# floppy_featherwing_rev_A.net
KiCad netlist of a schematic drawn in EAGLE
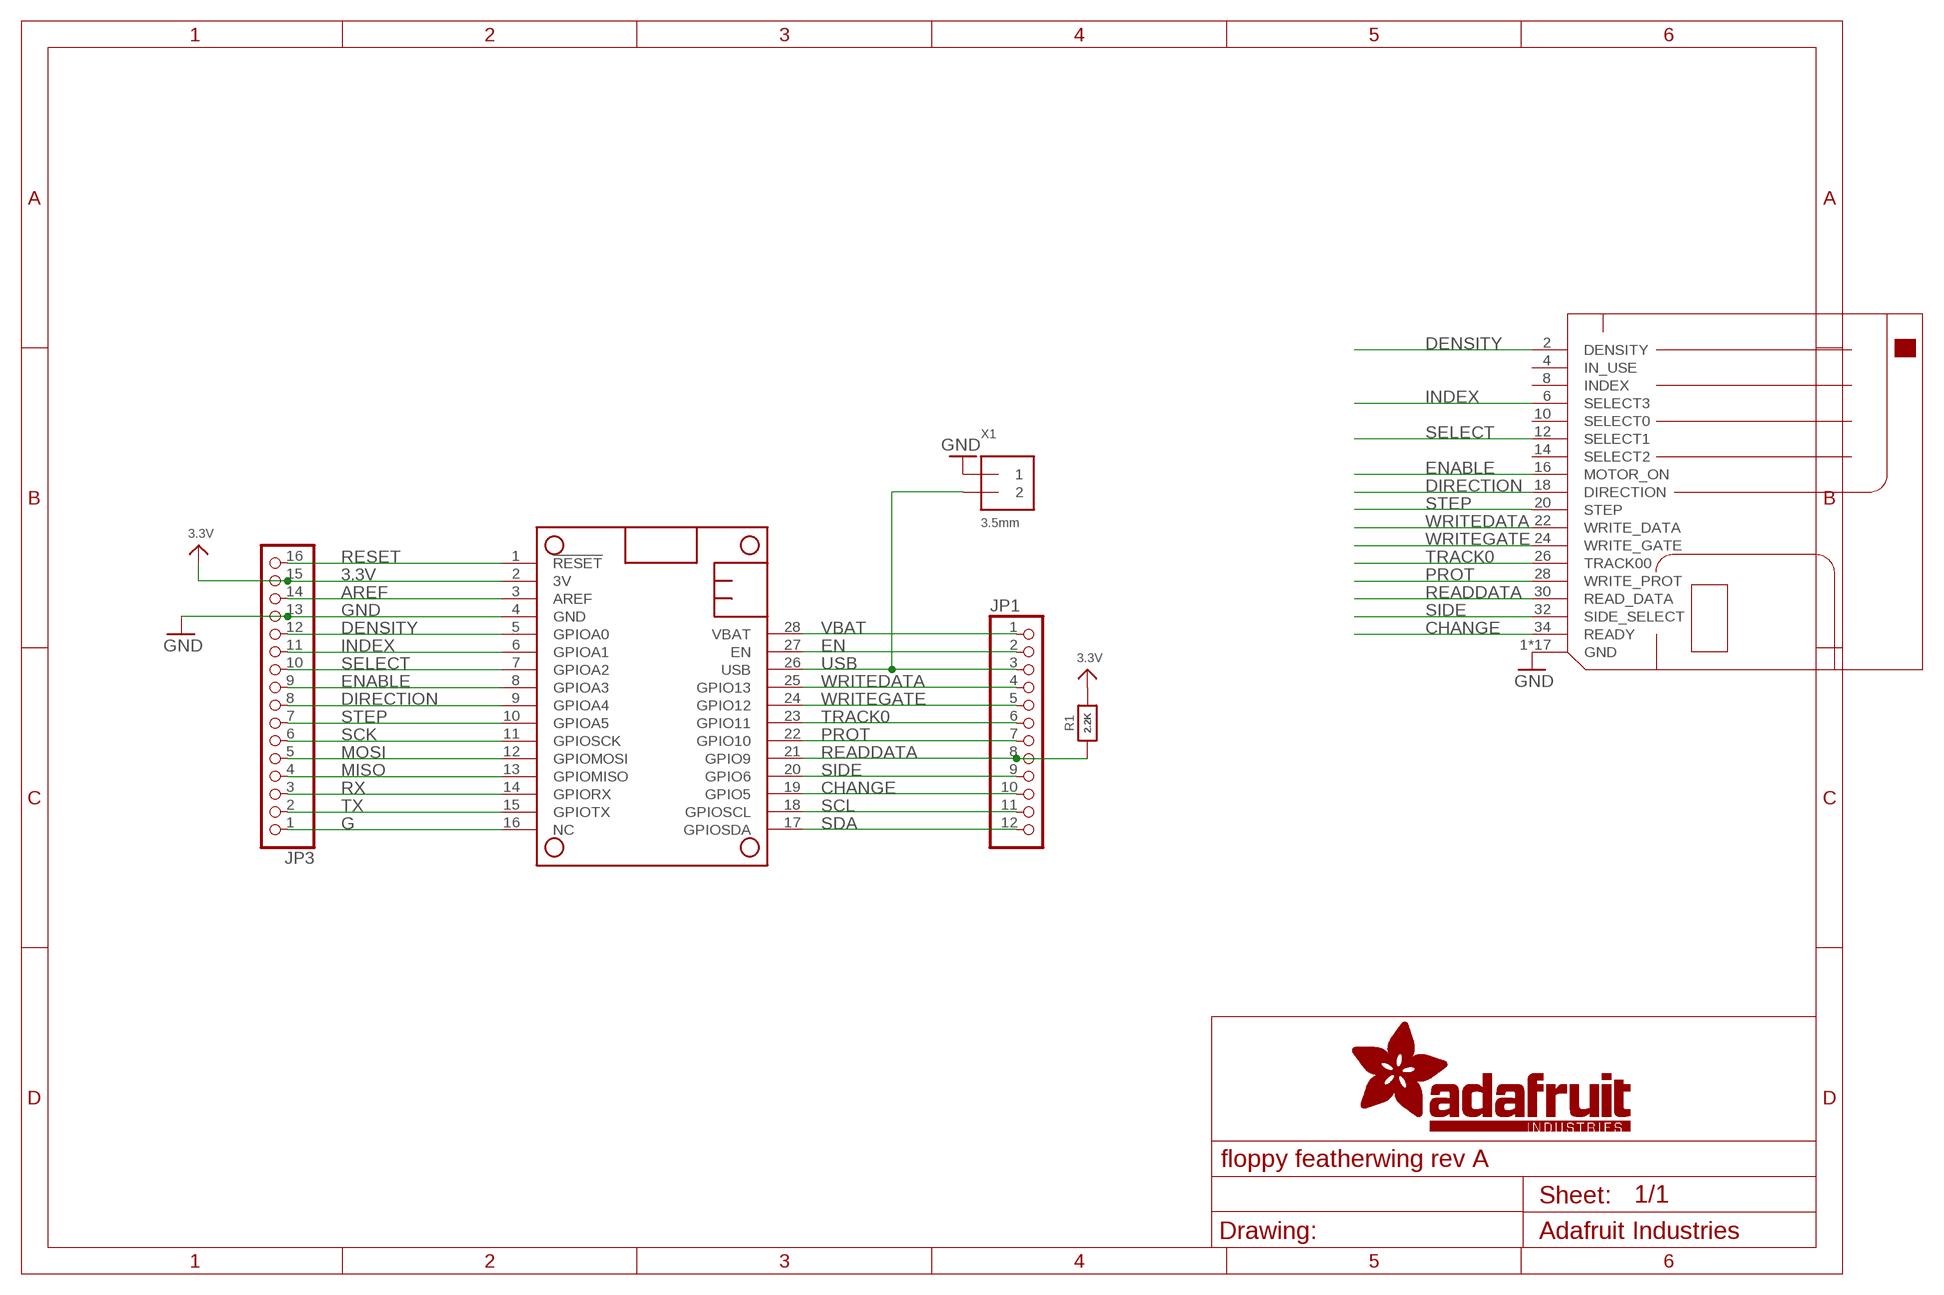
[diagram p0: schematic, sheet 1]

(export (version "E")
  (design (tool "Eeschema 10.0.6"))
  (components
    (comp (ref "FDD1")
      (value "FLOPPY_IDC_SHROUDED")
      (footprint "eagle-import:2X17_FLOPPY_IDC")
      (libsource (lib "eagle-import") (part "FLOPPY_IDC_SHROUDED"))
    )
    (comp (ref "JP1")
      (value "HEADER-1X12")
      (footprint "eagle-import:1X12_ROUND")
      (libsource (lib "eagle-import") (part "HEADER-1X12"))
    )
    (comp (ref "JP3")
      (value "HEADER-1X16ROUND")
      (footprint "eagle-import:1X16_ROUND")
      (libsource (lib "eagle-import") (part "HEADER-1X16ROUND"))
    )
    (comp (ref "MS1")
      (value "FEATHERWING")
      (footprint "eagle-import:FEATHERWING")
      (libsource (lib "eagle-import") (part "FEATHERWING"))
    )
    (comp (ref "R1")
      (value "2.2K")
      (footprint "eagle-import:0805-NO")
      (libsource (lib "eagle-import") (part "RESISTOR0805_NOOUTLINE"))
    )
    (comp (ref "X1")
      (value "3.5mm")
      (footprint "eagle-import:TERMBLOCK_1X2-3.5MM")
      (libsource (lib "eagle-import") (part "TERMBLOCK_1X2_3.5MM"))
    )
  )
  (nets
    (net (code "1") (name "/AREF") (class "Default")
      (node (ref "JP3") (pin "14") (pinfunction "14_14") (pintype "passive"))
      (node (ref "MS1") (pin "3") (pinfunction "AREF_3") (pintype "passive"))
    )
    (net (code "2") (name "/CHANGE") (class "Default")
      (node (ref "FDD1") (pin "34") (pinfunction "READY_34") (pintype "output"))
      (node (ref "JP1") (pin "10") (pinfunction "10_10") (pintype "passive"))
      (node (ref "MS1") (pin "19") (pinfunction "GPIO5_19") (pintype "bidirectional"))
    )
    (net (code "3") (name "/DENSITY") (class "Default")
      (node (ref "FDD1") (pin "2") (pinfunction "DENSITY_2") (pintype "input"))
      (node (ref "JP3") (pin "12") (pinfunction "12_12") (pintype "passive"))
      (node (ref "MS1") (pin "5") (pinfunction "GPIOA0_5") (pintype "bidirectional"))
    )
    (net (code "4") (name "/DIRECTION") (class "Default")
      (node (ref "FDD1") (pin "18") (pinfunction "DIRECTION_18") (pintype "input"))
      (node (ref "JP3") (pin "8") (pinfunction "8_8") (pintype "passive"))
      (node (ref "MS1") (pin "9") (pinfunction "GPIOA4_9") (pintype "bidirectional"))
    )
    (net (code "5") (name "/EN") (class "Default")
      (node (ref "JP1") (pin "2") (pinfunction "2_2") (pintype "passive"))
      (node (ref "MS1") (pin "27") (pinfunction "EN_27") (pintype "passive"))
    )
    (net (code "6") (name "/ENABLE") (class "Default")
      (node (ref "FDD1") (pin "16") (pinfunction "MOTOR_ON_16") (pintype "input"))
      (node (ref "JP3") (pin "9") (pinfunction "9_9") (pintype "passive"))
      (node (ref "MS1") (pin "8") (pinfunction "GPIOA3_8") (pintype "bidirectional"))
    )
    (net (code "7") (name "/G") (class "Default")
      (node (ref "JP3") (pin "1") (pinfunction "1_1") (pintype "passive"))
      (node (ref "MS1") (pin "16") (pinfunction "NC_16") (pintype "passive"))
    )
    (net (code "8") (name "/INDEX") (class "Default")
      (node (ref "FDD1") (pin "6") (pinfunction "SELECT3_6") (pintype "input"))
      (node (ref "JP3") (pin "11") (pinfunction "11_11") (pintype "passive"))
      (node (ref "MS1") (pin "6") (pinfunction "GPIOA1_6") (pintype "bidirectional"))
    )
    (net (code "9") (name "/MISO") (class "Default")
      (node (ref "JP3") (pin "4") (pinfunction "4_4") (pintype "passive"))
      (node (ref "MS1") (pin "13") (pinfunction "GPIOMISO_13") (pintype "bidirectional"))
    )
    (net (code "10") (name "/MOSI") (class "Default")
      (node (ref "JP3") (pin "5") (pinfunction "5_5") (pintype "passive"))
      (node (ref "MS1") (pin "12") (pinfunction "GPIOMOSI_12") (pintype "bidirectional"))
    )
    (net (code "11") (name "/PROT") (class "Default")
      (node (ref "FDD1") (pin "28") (pinfunction "WRITE_PROT_28") (pintype "output"))
      (node (ref "JP1") (pin "7") (pinfunction "7_7") (pintype "passive"))
      (node (ref "MS1") (pin "22") (pinfunction "GPIO10_22") (pintype "bidirectional"))
    )
    (net (code "12") (name "/READDATA") (class "Default")
      (node (ref "FDD1") (pin "30") (pinfunction "READ_DATA_30") (pintype "output"))
      (node (ref "JP1") (pin "8") (pinfunction "8_8") (pintype "passive"))
      (node (ref "MS1") (pin "21") (pinfunction "GPIO9_21") (pintype "bidirectional"))
      (node (ref "R1") (pin "1") (pinfunction "1_1") (pintype "passive"))
    )
    (net (code "13") (name "/RESET") (class "Default")
      (node (ref "JP3") (pin "16") (pinfunction "16_16") (pintype "passive"))
      (node (ref "MS1") (pin "1") (pinfunction "~{RESET}_1") (pintype "input"))
    )
    (net (code "14") (name "/RX") (class "Default")
      (node (ref "JP3") (pin "3") (pinfunction "3_3") (pintype "passive"))
      (node (ref "MS1") (pin "14") (pinfunction "GPIORX_14") (pintype "bidirectional"))
    )
    (net (code "15") (name "/SCK") (class "Default")
      (node (ref "JP3") (pin "6") (pinfunction "6_6") (pintype "passive"))
      (node (ref "MS1") (pin "11") (pinfunction "GPIOSCK_11") (pintype "bidirectional"))
    )
    (net (code "16") (name "/SCL") (class "Default")
      (node (ref "JP1") (pin "11") (pinfunction "11_11") (pintype "passive"))
      (node (ref "MS1") (pin "18") (pinfunction "GPIOSCL_18") (pintype "bidirectional"))
    )
    (net (code "17") (name "/SDA") (class "Default")
      (node (ref "JP1") (pin "12") (pinfunction "12_12") (pintype "passive"))
      (node (ref "MS1") (pin "17") (pinfunction "GPIOSDA_17") (pintype "bidirectional"))
    )
    (net (code "18") (name "/SELECT") (class "Default")
      (node (ref "FDD1") (pin "12") (pinfunction "SELECT1_12") (pintype "input"))
      (node (ref "JP3") (pin "10") (pinfunction "10_10") (pintype "passive"))
      (node (ref "MS1") (pin "7") (pinfunction "GPIOA2_7") (pintype "bidirectional"))
    )
    (net (code "19") (name "/SIDE") (class "Default")
      (node (ref "FDD1") (pin "32") (pinfunction "SIDE_SELECT_32") (pintype "input"))
      (node (ref "JP1") (pin "9") (pinfunction "9_9") (pintype "passive"))
      (node (ref "MS1") (pin "20") (pinfunction "GPIO6_20") (pintype "bidirectional"))
    )
    (net (code "20") (name "/STEP") (class "Default")
      (node (ref "FDD1") (pin "20") (pinfunction "STEP_20") (pintype "input"))
      (node (ref "JP3") (pin "7") (pinfunction "7_7") (pintype "passive"))
      (node (ref "MS1") (pin "10") (pinfunction "GPIOA5_10") (pintype "bidirectional"))
    )
    (net (code "21") (name "/TRACK0") (class "Default")
      (node (ref "FDD1") (pin "26") (pinfunction "TRACK00_26") (pintype "output"))
      (node (ref "JP1") (pin "6") (pinfunction "6_6") (pintype "passive"))
      (node (ref "MS1") (pin "23") (pinfunction "GPIO11_23") (pintype "bidirectional"))
    )
    (net (code "22") (name "/TX") (class "Default")
      (node (ref "JP3") (pin "2") (pinfunction "2_2") (pintype "passive"))
      (node (ref "MS1") (pin "15") (pinfunction "GPIOTX_15") (pintype "bidirectional"))
    )
    (net (code "23") (name "/USB") (class "Default")
      (node (ref "JP1") (pin "3") (pinfunction "3_3") (pintype "passive"))
      (node (ref "MS1") (pin "26") (pinfunction "USB_26") (pintype "power_in"))
      (node (ref "X1") (pin "2") (pinfunction "2_2") (pintype "passive"))
    )
    (net (code "24") (name "/VBAT") (class "Default")
      (node (ref "JP1") (pin "1") (pinfunction "1_1") (pintype "passive"))
      (node (ref "MS1") (pin "28") (pinfunction "VBAT_28") (pintype "power_in"))
    )
    (net (code "25") (name "/WRITEDATA") (class "Default")
      (node (ref "FDD1") (pin "22") (pinfunction "WRITE_DATA_22") (pintype "input"))
      (node (ref "JP1") (pin "4") (pinfunction "4_4") (pintype "passive"))
      (node (ref "MS1") (pin "25") (pinfunction "GPIO13_25") (pintype "bidirectional"))
    )
    (net (code "26") (name "/WRITEGATE") (class "Default")
      (node (ref "FDD1") (pin "24") (pinfunction "WRITE_GATE_24") (pintype "input"))
      (node (ref "JP1") (pin "5") (pinfunction "5_5") (pintype "passive"))
      (node (ref "MS1") (pin "24") (pinfunction "GPIO12_24") (pintype "bidirectional"))
    )
    (net (code "27") (name "3.3V") (class "Default")
      (node (ref "JP3") (pin "15") (pinfunction "15_15") (pintype "passive"))
      (node (ref "MS1") (pin "2") (pinfunction "3V_2") (pintype "power_in"))
      (node (ref "R1") (pin "2") (pinfunction "2_2") (pintype "passive"))
    )
    (net (code "28") (name "GND") (class "Default")
      (node (ref "FDD1") (pin "1") (pinfunction "GND_1") (pintype "power_in"))
      (node (ref "FDD1") (pin "11") (pinfunction "GND_11") (pintype "power_in"))
      (node (ref "FDD1") (pin "13") (pinfunction "GND_13") (pintype "power_in"))
      (node (ref "FDD1") (pin "15") (pinfunction "GND_15") (pintype "power_in"))
      (node (ref "FDD1") (pin "17") (pinfunction "GND_17") (pintype "power_in"))
      (node (ref "FDD1") (pin "19") (pinfunction "GND_19") (pintype "power_in"))
      (node (ref "FDD1") (pin "21") (pinfunction "GND_21") (pintype "power_in"))
      (node (ref "FDD1") (pin "23") (pinfunction "GND_23") (pintype "power_in"))
      (node (ref "FDD1") (pin "25") (pinfunction "GND_25") (pintype "power_in"))
      (node (ref "FDD1") (pin "27") (pinfunction "GND_27") (pintype "power_in"))
      (node (ref "FDD1") (pin "29") (pinfunction "GND_29") (pintype "power_in"))
      (node (ref "FDD1") (pin "3") (pinfunction "GND_3") (pintype "power_in"))
      (node (ref "FDD1") (pin "31") (pinfunction "GND_31") (pintype "power_in"))
      (node (ref "FDD1") (pin "33") (pinfunction "GND_33") (pintype "power_in"))
      (node (ref "FDD1") (pin "5") (pinfunction "GND_5") (pintype "power_in"))
      (node (ref "FDD1") (pin "7") (pinfunction "GND_7") (pintype "power_in"))
      (node (ref "FDD1") (pin "9") (pinfunction "GND_9") (pintype "power_in"))
      (node (ref "JP3") (pin "13") (pinfunction "13_13") (pintype "passive"))
      (node (ref "MS1") (pin "4") (pinfunction "GND_4") (pintype "power_in"))
      (node (ref "X1") (pin "1") (pinfunction "1_1") (pintype "passive"))
    )
    (net (code "29") (name "unconnected-(FDD1-INDEX-Pad8)") (class "Default")
      (node (ref "FDD1") (pin "8") (pinfunction "INDEX_8") (pintype "output"))
    )
    (net (code "30") (name "unconnected-(FDD1-IN_USE-Pad4)") (class "Default")
      (node (ref "FDD1") (pin "4") (pinfunction "IN_USE_4") (pintype "input"))
    )
    (net (code "31") (name "unconnected-(FDD1-SELECT0-Pad10)") (class "Default")
      (node (ref "FDD1") (pin "10") (pinfunction "SELECT0_10") (pintype "input"))
    )
    (net (code "32") (name "unconnected-(FDD1-SELECT2-Pad14)") (class "Default")
      (node (ref "FDD1") (pin "14") (pinfunction "SELECT2_14") (pintype "input"))
    )
  )
)
